# athf-er.net
KiCad netlist of a schematic drawn in EAGLE
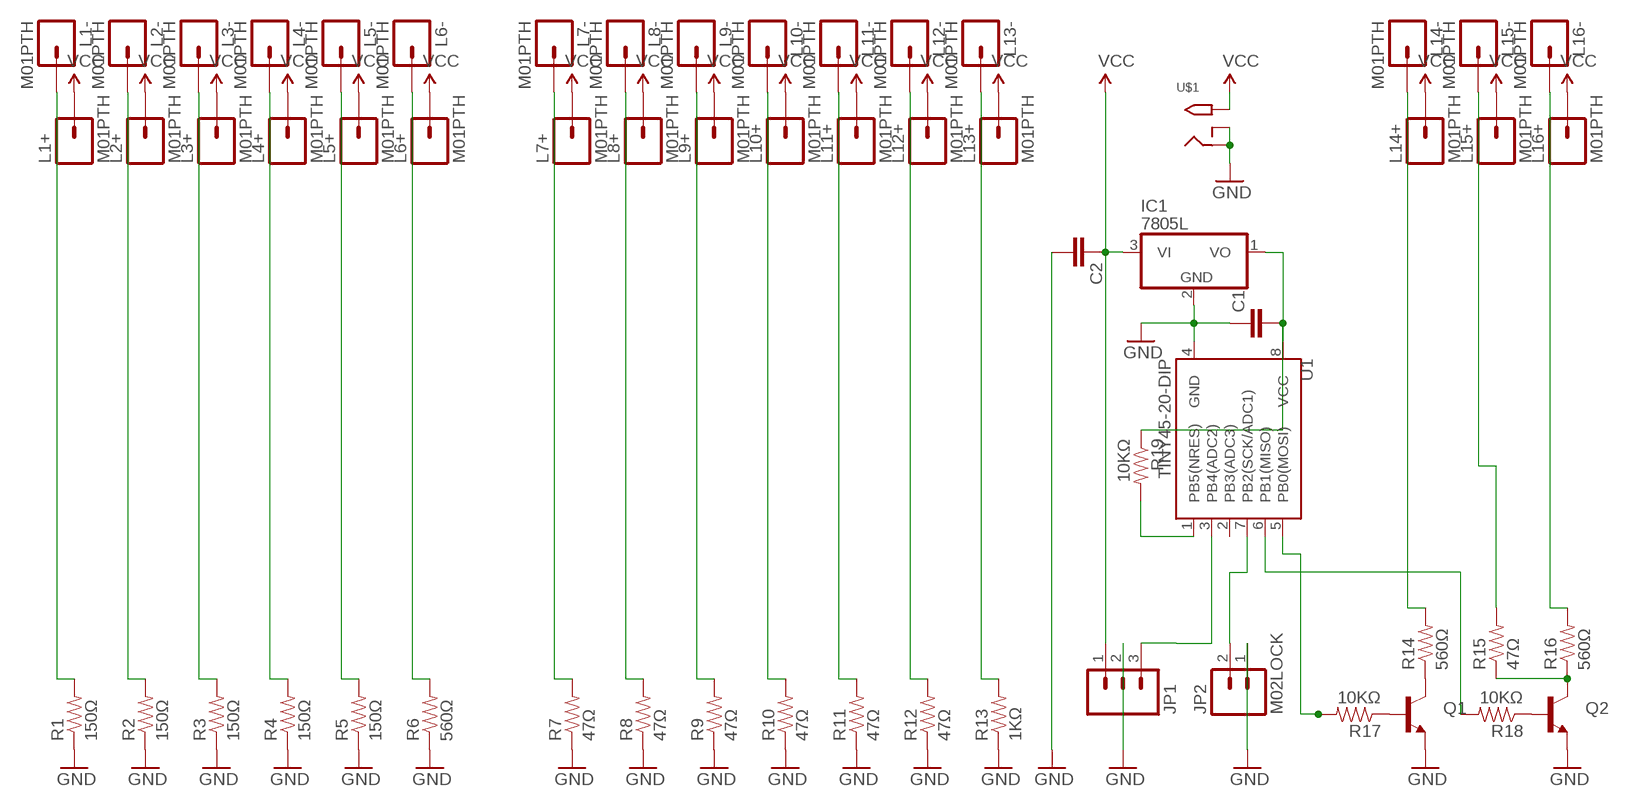
[diagram p0: schematic, sheet 1]

(export (version "E")
  (design (tool "Eeschema 10.0.6"))
  (components
    (comp (ref "C1")
      (value "CAPEZ")
      (footprint "eagle-import:CAP-PTH-SMALLEZ")
      (libsource (lib "eagle-import") (part "CAPEZ"))
    )
    (comp (ref "C2")
      (value "CAPEZ")
      (footprint "eagle-import:CAP-PTH-SMALLEZ")
      (libsource (lib "eagle-import") (part "CAPEZ"))
    )
    (comp (ref "IC1")
      (value "7805L")
      (footprint "eagle-import:TO92")
      (libsource (lib "eagle-import") (part "78L05"))
    )
    (comp (ref "JP1")
      (value "M03LOCK")
      (footprint "eagle-import:1X03_LOCK")
      (libsource (lib "eagle-import") (part "M03LOCK"))
    )
    (comp (ref "JP2")
      (value "M02LOCK")
      (footprint "eagle-import:1X02_LOCK")
      (libsource (lib "eagle-import") (part "M02LOCK"))
    )
    (comp (ref "L1+")
      (value "M01PTH")
      (footprint "eagle-import:1X01")
      (libsource (lib "eagle-import") (part "M01PTH"))
    )
    (comp (ref "L1-")
      (value "M01PTH")
      (footprint "eagle-import:1X01")
      (libsource (lib "eagle-import") (part "M01PTH"))
    )
    (comp (ref "L2+")
      (value "M01PTH")
      (footprint "eagle-import:1X01")
      (libsource (lib "eagle-import") (part "M01PTH"))
    )
    (comp (ref "L2-")
      (value "M01PTH")
      (footprint "eagle-import:1X01")
      (libsource (lib "eagle-import") (part "M01PTH"))
    )
    (comp (ref "L3+")
      (value "M01PTH")
      (footprint "eagle-import:1X01")
      (libsource (lib "eagle-import") (part "M01PTH"))
    )
    (comp (ref "L3-")
      (value "M01PTH")
      (footprint "eagle-import:1X01")
      (libsource (lib "eagle-import") (part "M01PTH"))
    )
    (comp (ref "L4+")
      (value "M01PTH")
      (footprint "eagle-import:1X01")
      (libsource (lib "eagle-import") (part "M01PTH"))
    )
    (comp (ref "L4-")
      (value "M01PTH")
      (footprint "eagle-import:1X01")
      (libsource (lib "eagle-import") (part "M01PTH"))
    )
    (comp (ref "L5+")
      (value "M01PTH")
      (footprint "eagle-import:1X01")
      (libsource (lib "eagle-import") (part "M01PTH"))
    )
    (comp (ref "L5-")
      (value "M01PTH")
      (footprint "eagle-import:1X01")
      (libsource (lib "eagle-import") (part "M01PTH"))
    )
    (comp (ref "L6+")
      (value "M01PTH")
      (footprint "eagle-import:1X01")
      (libsource (lib "eagle-import") (part "M01PTH"))
    )
    (comp (ref "L6-")
      (value "M01PTH")
      (footprint "eagle-import:1X01")
      (libsource (lib "eagle-import") (part "M01PTH"))
    )
    (comp (ref "L7+")
      (value "M01PTH")
      (footprint "eagle-import:1X01")
      (libsource (lib "eagle-import") (part "M01PTH"))
    )
    (comp (ref "L7-")
      (value "M01PTH")
      (footprint "eagle-import:1X01")
      (libsource (lib "eagle-import") (part "M01PTH"))
    )
    (comp (ref "L8+")
      (value "M01PTH")
      (footprint "eagle-import:1X01")
      (libsource (lib "eagle-import") (part "M01PTH"))
    )
    (comp (ref "L8-")
      (value "M01PTH")
      (footprint "eagle-import:1X01")
      (libsource (lib "eagle-import") (part "M01PTH"))
    )
    (comp (ref "L9+")
      (value "M01PTH")
      (footprint "eagle-import:1X01")
      (libsource (lib "eagle-import") (part "M01PTH"))
    )
    (comp (ref "L9-")
      (value "M01PTH")
      (footprint "eagle-import:1X01")
      (libsource (lib "eagle-import") (part "M01PTH"))
    )
    (comp (ref "L10+")
      (value "M01PTH")
      (footprint "eagle-import:1X01")
      (libsource (lib "eagle-import") (part "M01PTH"))
    )
    (comp (ref "L10-")
      (value "M01PTH")
      (footprint "eagle-import:1X01")
      (libsource (lib "eagle-import") (part "M01PTH"))
    )
    (comp (ref "L11+")
      (value "M01PTH")
      (footprint "eagle-import:1X01")
      (libsource (lib "eagle-import") (part "M01PTH"))
    )
    (comp (ref "L11-")
      (value "M01PTH")
      (footprint "eagle-import:1X01")
      (libsource (lib "eagle-import") (part "M01PTH"))
    )
    (comp (ref "L12+")
      (value "M01PTH")
      (footprint "eagle-import:1X01")
      (libsource (lib "eagle-import") (part "M01PTH"))
    )
    (comp (ref "L12-")
      (value "M01PTH")
      (footprint "eagle-import:1X01")
      (libsource (lib "eagle-import") (part "M01PTH"))
    )
    (comp (ref "L13+")
      (value "M01PTH")
      (footprint "eagle-import:1X01")
      (libsource (lib "eagle-import") (part "M01PTH"))
    )
    (comp (ref "L13-")
      (value "M01PTH")
      (footprint "eagle-import:1X01")
      (libsource (lib "eagle-import") (part "M01PTH"))
    )
    (comp (ref "L14+")
      (value "M01PTH")
      (footprint "eagle-import:1X01")
      (libsource (lib "eagle-import") (part "M01PTH"))
    )
    (comp (ref "L14-")
      (value "M01PTH")
      (footprint "eagle-import:1X01")
      (libsource (lib "eagle-import") (part "M01PTH"))
    )
    (comp (ref "L15+")
      (value "M01PTH")
      (footprint "eagle-import:1X01")
      (libsource (lib "eagle-import") (part "M01PTH"))
    )
    (comp (ref "L15-")
      (value "M01PTH")
      (footprint "eagle-import:1X01")
      (libsource (lib "eagle-import") (part "M01PTH"))
    )
    (comp (ref "L16+")
      (value "M01PTH")
      (footprint "eagle-import:1X01")
      (libsource (lib "eagle-import") (part "M01PTH"))
    )
    (comp (ref "L16-")
      (value "M01PTH")
      (footprint "eagle-import:1X01")
      (libsource (lib "eagle-import") (part "M01PTH"))
    )
    (comp (ref "Q1")
      (value "TRANSISTOR_NPNTO92")
      (footprint "eagle-import:TO-92")
      (libsource (lib "eagle-import") (part "TRANSISTOR_NPNTO92"))
    )
    (comp (ref "Q2")
      (value "TRANSISTOR_NPNTO92")
      (footprint "eagle-import:TO-92")
      (libsource (lib "eagle-import") (part "TRANSISTOR_NPNTO92"))
    )
    (comp (ref "R1")
      (value "150Ω")
      (footprint "eagle-import:AXIAL-0.3EZ")
      (libsource (lib "eagle-import") (part "RESISTOREZ"))
    )
    (comp (ref "R2")
      (value "150Ω")
      (footprint "eagle-import:AXIAL-0.3EZ")
      (libsource (lib "eagle-import") (part "RESISTOREZ"))
    )
    (comp (ref "R3")
      (value "150Ω")
      (footprint "eagle-import:AXIAL-0.3EZ")
      (libsource (lib "eagle-import") (part "RESISTOREZ"))
    )
    (comp (ref "R4")
      (value "150Ω")
      (footprint "eagle-import:AXIAL-0.3EZ")
      (libsource (lib "eagle-import") (part "RESISTOREZ"))
    )
    (comp (ref "R5")
      (value "150Ω")
      (footprint "eagle-import:AXIAL-0.3EZ")
      (libsource (lib "eagle-import") (part "RESISTOREZ"))
    )
    (comp (ref "R6")
      (value "560Ω")
      (footprint "eagle-import:AXIAL-0.3EZ")
      (libsource (lib "eagle-import") (part "RESISTOREZ"))
    )
    (comp (ref "R7")
      (value "47Ω")
      (footprint "eagle-import:AXIAL-0.3EZ")
      (libsource (lib "eagle-import") (part "RESISTOREZ"))
    )
    (comp (ref "R8")
      (value "47Ω")
      (footprint "eagle-import:AXIAL-0.3EZ")
      (libsource (lib "eagle-import") (part "RESISTOREZ"))
    )
    (comp (ref "R9")
      (value "47Ω")
      (footprint "eagle-import:AXIAL-0.3EZ")
      (libsource (lib "eagle-import") (part "RESISTOREZ"))
    )
    (comp (ref "R10")
      (value "47Ω")
      (footprint "eagle-import:AXIAL-0.3EZ")
      (libsource (lib "eagle-import") (part "RESISTOREZ"))
    )
    (comp (ref "R11")
      (value "47Ω")
      (footprint "eagle-import:AXIAL-0.3EZ")
      (libsource (lib "eagle-import") (part "RESISTOREZ"))
    )
    (comp (ref "R12")
      (value "47Ω")
      (footprint "eagle-import:AXIAL-0.3EZ")
      (libsource (lib "eagle-import") (part "RESISTOREZ"))
    )
    (comp (ref "R13")
      (value "1KΩ")
      (footprint "eagle-import:AXIAL-0.3EZ")
      (libsource (lib "eagle-import") (part "RESISTOREZ"))
    )
    (comp (ref "R14")
      (value "560Ω")
      (footprint "eagle-import:AXIAL-0.3EZ")
      (libsource (lib "eagle-import") (part "RESISTOREZ"))
    )
    (comp (ref "R15")
      (value "47Ω")
      (footprint "eagle-import:AXIAL-0.3EZ")
      (libsource (lib "eagle-import") (part "RESISTOREZ"))
    )
    (comp (ref "R16")
      (value "560Ω")
      (footprint "eagle-import:AXIAL-0.3EZ")
      (libsource (lib "eagle-import") (part "RESISTOREZ"))
    )
    (comp (ref "R17")
      (value "10KΩ")
      (footprint "eagle-import:AXIAL-0.3EZ")
      (libsource (lib "eagle-import") (part "RESISTOREZ"))
    )
    (comp (ref "R18")
      (value "10KΩ")
      (footprint "eagle-import:AXIAL-0.3EZ")
      (libsource (lib "eagle-import") (part "RESISTOREZ"))
    )
    (comp (ref "R19")
      (value "10KΩ")
      (footprint "eagle-import:AXIAL-0.3EZ")
      (libsource (lib "eagle-import") (part "RESISTOREZ"))
    )
    (comp (ref "U$1")
      (value "2.1MMJACKTHM")
      (footprint "eagle-import:PJ-102A")
      (libsource (lib "eagle-import") (part "2.1MMJACKTHM"))
    )
    (comp (ref "U1")
      (value "TINY45-20-DIP")
      (footprint "eagle-import:DIP08")
      (libsource (lib "eagle-import") (part "ATTINY45TINY45-20-DIP"))
    )
  )
  (nets
    (net (code "1") (name "GND") (class "Default")
      (node (ref "C1") (pin "1") (pinfunction "1_1") (pintype "passive"))
      (node (ref "C2") (pin "2") (pinfunction "2_2") (pintype "passive"))
      (node (ref "IC1") (pin "2") (pinfunction "GND_2") (pintype "passive"))
      (node (ref "JP1") (pin "2") (pinfunction "2_2") (pintype "passive"))
      (node (ref "JP2") (pin "1") (pinfunction "1_1") (pintype "passive"))
      (node (ref "Q1") (pin "1") (pinfunction "E_1") (pintype "passive"))
      (node (ref "Q2") (pin "1") (pinfunction "E_1") (pintype "passive"))
      (node (ref "R1") (pin "P$1") (pinfunction "1_P$1") (pintype "passive"))
      (node (ref "R10") (pin "P$1") (pinfunction "1_P$1") (pintype "passive"))
      (node (ref "R11") (pin "P$1") (pinfunction "1_P$1") (pintype "passive"))
      (node (ref "R12") (pin "P$1") (pinfunction "1_P$1") (pintype "passive"))
      (node (ref "R13") (pin "P$1") (pinfunction "1_P$1") (pintype "passive"))
      (node (ref "R2") (pin "P$1") (pinfunction "1_P$1") (pintype "passive"))
      (node (ref "R3") (pin "P$1") (pinfunction "1_P$1") (pintype "passive"))
      (node (ref "R4") (pin "P$1") (pinfunction "1_P$1") (pintype "passive"))
      (node (ref "R5") (pin "P$1") (pinfunction "1_P$1") (pintype "passive"))
      (node (ref "R6") (pin "P$1") (pinfunction "1_P$1") (pintype "passive"))
      (node (ref "R7") (pin "P$1") (pinfunction "1_P$1") (pintype "passive"))
      (node (ref "R8") (pin "P$1") (pinfunction "1_P$1") (pintype "passive"))
      (node (ref "R9") (pin "P$1") (pinfunction "1_P$1") (pintype "passive"))
      (node (ref "U$1") (pin "RING") (pinfunction "RING_RING") (pintype "bidirectional"))
      (node (ref "U$1") (pin "RING_SW") (pinfunction "RING_SW_RING_SW") (pintype "bidirectional"))
      (node (ref "U1") (pin "4") (pinfunction "GND_4") (pintype "bidirectional"))
    )
    (net (code "2") (name "Net-(IC1-VO)") (class "Default")
      (node (ref "C1") (pin "2") (pinfunction "2_2") (pintype "passive"))
      (node (ref "IC1") (pin "1") (pinfunction "VO_1") (pintype "passive"))
      (node (ref "R19") (pin "P$1") (pinfunction "1_P$1") (pintype "passive"))
      (node (ref "U1") (pin "8") (pinfunction "VCC_8") (pintype "bidirectional"))
    )
    (net (code "3") (name "Net-(Q1-B)") (class "Default")
      (node (ref "Q1") (pin "2") (pinfunction "B_2") (pintype "passive"))
      (node (ref "R17") (pin "P$1") (pinfunction "1_P$1") (pintype "passive"))
    )
    (net (code "4") (name "Net-(Q1-C)") (class "Default")
      (node (ref "Q1") (pin "3") (pinfunction "C_3") (pintype "passive"))
      (node (ref "R14") (pin "P$1") (pinfunction "1_P$1") (pintype "passive"))
    )
    (net (code "5") (name "Net-(Q2-B)") (class "Default")
      (node (ref "Q2") (pin "2") (pinfunction "B_2") (pintype "passive"))
      (node (ref "R18") (pin "P$1") (pinfunction "1_P$1") (pintype "passive"))
    )
    (net (code "6") (name "Net-(Q2-C)") (class "Default")
      (node (ref "Q2") (pin "3") (pinfunction "C_3") (pintype "passive"))
      (node (ref "R15") (pin "P$1") (pinfunction "1_P$1") (pintype "passive"))
      (node (ref "R16") (pin "P$1") (pinfunction "1_P$1") (pintype "passive"))
    )
    (net (code "7") (name "Net-(R1-2)") (class "Default")
      (node (ref "L1-") (pin "1") (pinfunction "1_1") (pintype "passive"))
      (node (ref "R1") (pin "P$2") (pinfunction "2_P$2") (pintype "passive"))
    )
    (net (code "8") (name "Net-(R2-2)") (class "Default")
      (node (ref "L2-") (pin "1") (pinfunction "1_1") (pintype "passive"))
      (node (ref "R2") (pin "P$2") (pinfunction "2_P$2") (pintype "passive"))
    )
    (net (code "9") (name "Net-(R3-2)") (class "Default")
      (node (ref "L3-") (pin "1") (pinfunction "1_1") (pintype "passive"))
      (node (ref "R3") (pin "P$2") (pinfunction "2_P$2") (pintype "passive"))
    )
    (net (code "10") (name "Net-(R4-2)") (class "Default")
      (node (ref "L4-") (pin "1") (pinfunction "1_1") (pintype "passive"))
      (node (ref "R4") (pin "P$2") (pinfunction "2_P$2") (pintype "passive"))
    )
    (net (code "11") (name "Net-(R5-2)") (class "Default")
      (node (ref "L5-") (pin "1") (pinfunction "1_1") (pintype "passive"))
      (node (ref "R5") (pin "P$2") (pinfunction "2_P$2") (pintype "passive"))
    )
    (net (code "12") (name "Net-(R6-2)") (class "Default")
      (node (ref "L6-") (pin "1") (pinfunction "1_1") (pintype "passive"))
      (node (ref "R6") (pin "P$2") (pinfunction "2_P$2") (pintype "passive"))
    )
    (net (code "13") (name "Net-(R7-2)") (class "Default")
      (node (ref "L7-") (pin "1") (pinfunction "1_1") (pintype "passive"))
      (node (ref "R7") (pin "P$2") (pinfunction "2_P$2") (pintype "passive"))
    )
    (net (code "14") (name "Net-(R8-2)") (class "Default")
      (node (ref "L8-") (pin "1") (pinfunction "1_1") (pintype "passive"))
      (node (ref "R8") (pin "P$2") (pinfunction "2_P$2") (pintype "passive"))
    )
    (net (code "15") (name "Net-(R9-2)") (class "Default")
      (node (ref "L9-") (pin "1") (pinfunction "1_1") (pintype "passive"))
      (node (ref "R9") (pin "P$2") (pinfunction "2_P$2") (pintype "passive"))
    )
    (net (code "16") (name "Net-(R10-2)") (class "Default")
      (node (ref "L10-") (pin "1") (pinfunction "1_1") (pintype "passive"))
      (node (ref "R10") (pin "P$2") (pinfunction "2_P$2") (pintype "passive"))
    )
    (net (code "17") (name "Net-(R11-2)") (class "Default")
      (node (ref "L11-") (pin "1") (pinfunction "1_1") (pintype "passive"))
      (node (ref "R11") (pin "P$2") (pinfunction "2_P$2") (pintype "passive"))
    )
    (net (code "18") (name "Net-(R12-2)") (class "Default")
      (node (ref "L12-") (pin "1") (pinfunction "1_1") (pintype "passive"))
      (node (ref "R12") (pin "P$2") (pinfunction "2_P$2") (pintype "passive"))
    )
    (net (code "19") (name "Net-(R13-2)") (class "Default")
      (node (ref "L13-") (pin "1") (pinfunction "1_1") (pintype "passive"))
      (node (ref "R13") (pin "P$2") (pinfunction "2_P$2") (pintype "passive"))
    )
    (net (code "20") (name "Net-(R14-2)") (class "Default")
      (node (ref "L14-") (pin "1") (pinfunction "1_1") (pintype "passive"))
      (node (ref "R14") (pin "P$2") (pinfunction "2_P$2") (pintype "passive"))
    )
    (net (code "21") (name "Net-(R15-2)") (class "Default")
      (node (ref "L15-") (pin "1") (pinfunction "1_1") (pintype "passive"))
      (node (ref "R15") (pin "P$2") (pinfunction "2_P$2") (pintype "passive"))
    )
    (net (code "22") (name "Net-(R16-2)") (class "Default")
      (node (ref "L16-") (pin "1") (pinfunction "1_1") (pintype "passive"))
      (node (ref "R16") (pin "P$2") (pinfunction "2_P$2") (pintype "passive"))
    )
    (net (code "23") (name "Net-(R17-2)") (class "Default")
      (node (ref "R17") (pin "P$2") (pinfunction "2_P$2") (pintype "passive"))
      (node (ref "U1") (pin "5") (pinfunction "PB0(MOSI)_5") (pintype "bidirectional"))
    )
    (net (code "24") (name "Net-(R18-2)") (class "Default")
      (node (ref "R18") (pin "P$2") (pinfunction "2_P$2") (pintype "passive"))
      (node (ref "U1") (pin "6") (pinfunction "PB1(MISO)_6") (pintype "bidirectional"))
    )
    (net (code "25") (name "Net-(R19-2)") (class "Default")
      (node (ref "R19") (pin "P$2") (pinfunction "2_P$2") (pintype "passive"))
      (node (ref "U1") (pin "1") (pinfunction "PB5(NRES)_1") (pintype "bidirectional"))
    )
    (net (code "26") (name "Net-(U1-PB2(SCK{slash}ADC1))") (class "Default")
      (node (ref "JP2") (pin "2") (pinfunction "2_2") (pintype "passive"))
      (node (ref "U1") (pin "7") (pinfunction "PB2(SCK/ADC1)_7") (pintype "bidirectional"))
    )
    (net (code "27") (name "Net-(U1-PB4(ADC2))") (class "Default")
      (node (ref "JP1") (pin "3") (pinfunction "3_3") (pintype "passive"))
      (node (ref "U1") (pin "3") (pinfunction "PB4(ADC2)_3") (pintype "bidirectional"))
    )
    (net (code "28") (name "VCC") (class "Default")
      (node (ref "C2") (pin "1") (pinfunction "1_1") (pintype "passive"))
      (node (ref "IC1") (pin "3") (pinfunction "VI_3") (pintype "input"))
      (node (ref "JP1") (pin "1") (pinfunction "1_1") (pintype "passive"))
      (node (ref "L1+") (pin "1") (pinfunction "1_1") (pintype "passive"))
      (node (ref "L10+") (pin "1") (pinfunction "1_1") (pintype "passive"))
      (node (ref "L11+") (pin "1") (pinfunction "1_1") (pintype "passive"))
      (node (ref "L12+") (pin "1") (pinfunction "1_1") (pintype "passive"))
      (node (ref "L13+") (pin "1") (pinfunction "1_1") (pintype "passive"))
      (node (ref "L14+") (pin "1") (pinfunction "1_1") (pintype "passive"))
      (node (ref "L15+") (pin "1") (pinfunction "1_1") (pintype "passive"))
      (node (ref "L16+") (pin "1") (pinfunction "1_1") (pintype "passive"))
      (node (ref "L2+") (pin "1") (pinfunction "1_1") (pintype "passive"))
      (node (ref "L3+") (pin "1") (pinfunction "1_1") (pintype "passive"))
      (node (ref "L4+") (pin "1") (pinfunction "1_1") (pintype "passive"))
      (node (ref "L5+") (pin "1") (pinfunction "1_1") (pintype "passive"))
      (node (ref "L6+") (pin "1") (pinfunction "1_1") (pintype "passive"))
      (node (ref "L7+") (pin "1") (pinfunction "1_1") (pintype "passive"))
      (node (ref "L8+") (pin "1") (pinfunction "1_1") (pintype "passive"))
      (node (ref "L9+") (pin "1") (pinfunction "1_1") (pintype "passive"))
      (node (ref "U$1") (pin "TIP") (pinfunction "TIP_TIP") (pintype "bidirectional"))
    )
    (net (code "29") (name "unconnected-(U1-PB3(ADC3)-Pad2)") (class "Default")
      (node (ref "U1") (pin "2") (pinfunction "PB3(ADC3)_2") (pintype "bidirectional"))
    )
  )
)
